# bb-psu-mk-1_2.net
KiCad netlist of a schematic drawn in EAGLE
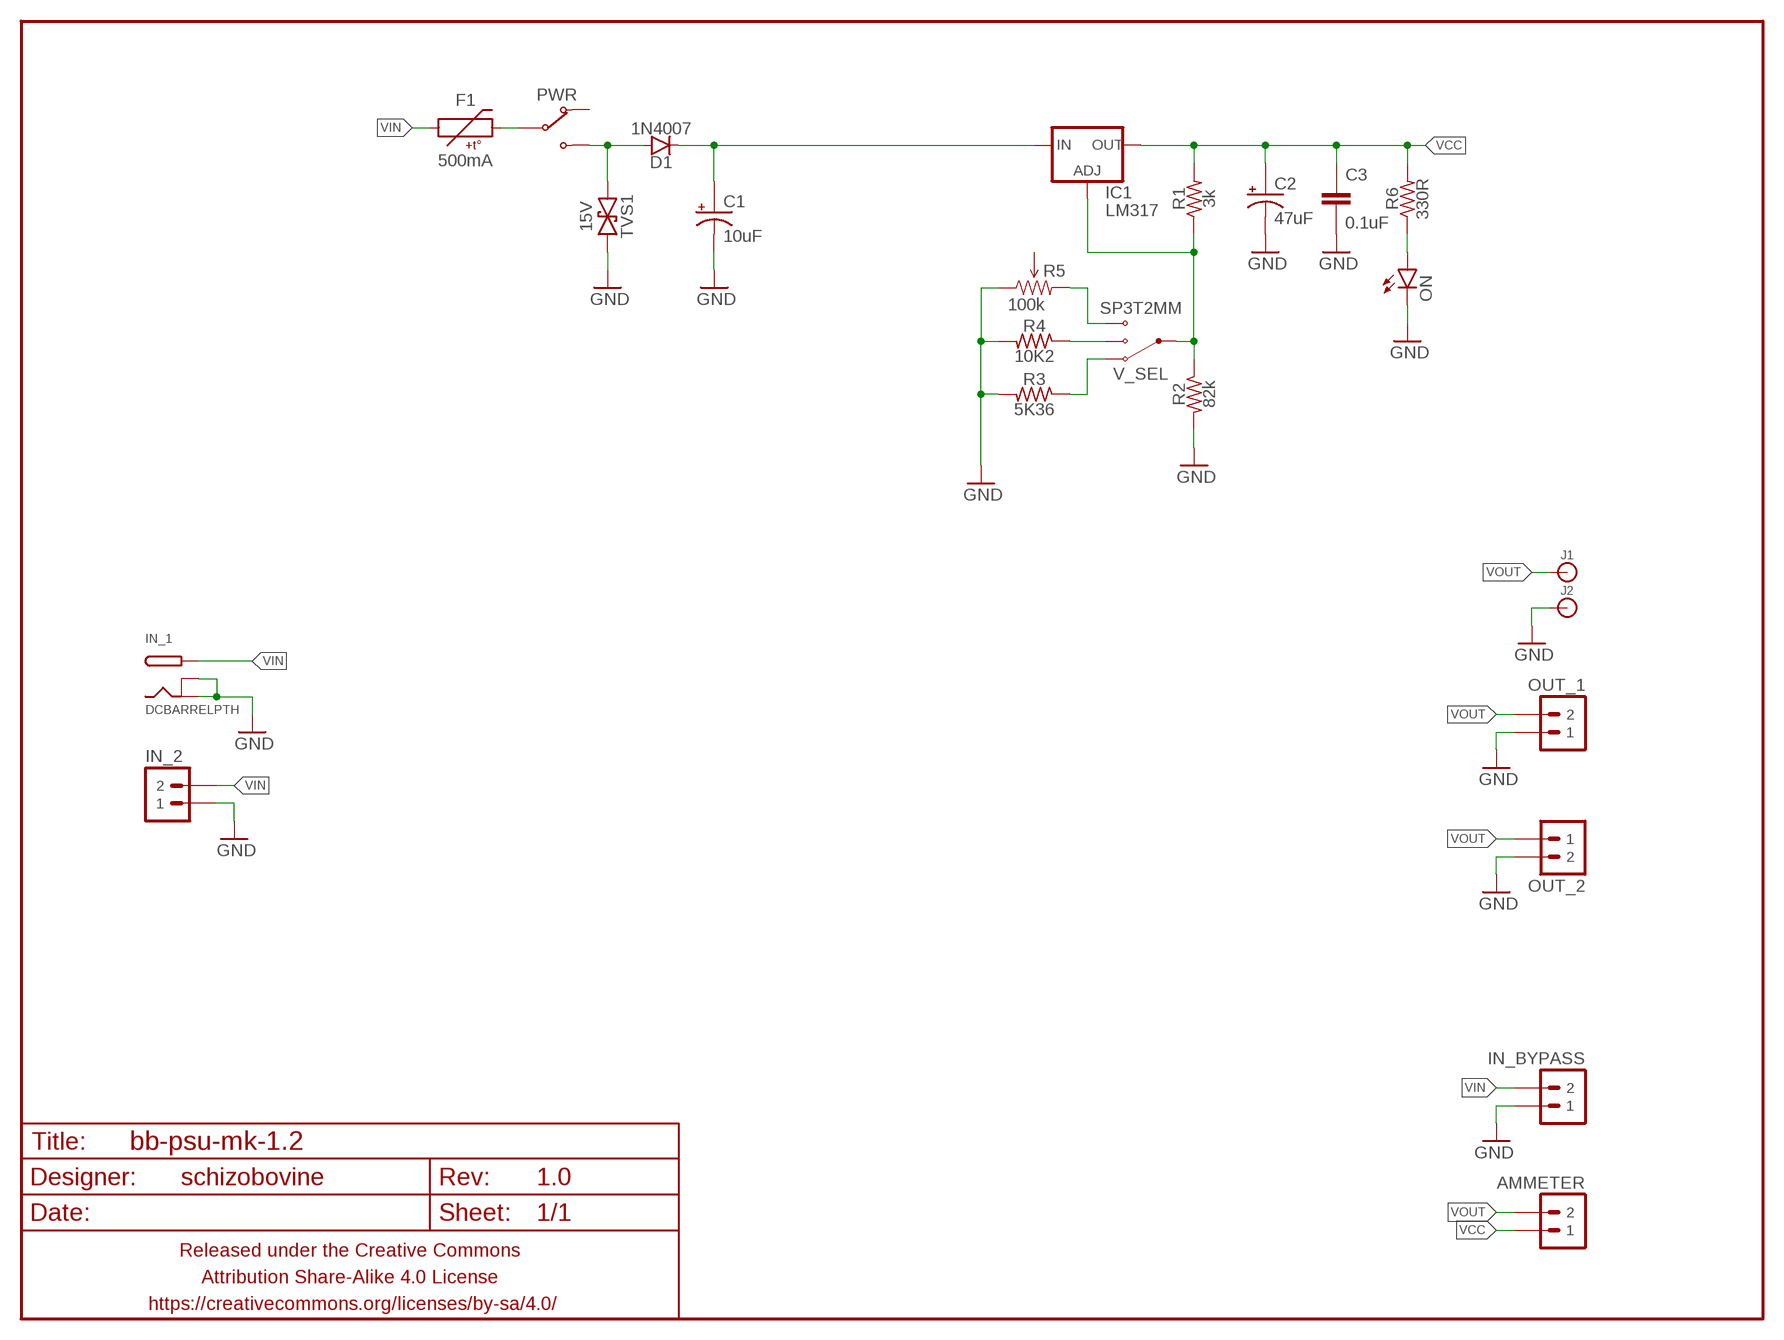
[diagram p0: schematic, sheet 1]

(export (version "E")
  (design (tool "Eeschema 10.0.6"))
  (components
    (comp (ref "AMMETER")
      (value "M02PTH-CENTERED")
      (footprint "eagle-import:1X02-CENTER")
      (libsource (lib "eagle-import") (part "M02PTH-CENTERED"))
    )
    (comp (ref "C1")
      (value "10uF")
      (footprint "eagle-import:E2,5-6")
      (libsource (lib "eagle-import") (part "CAPACITOR-POLARIZEDE2.5-6"))
    )
    (comp (ref "C2")
      (value "47uF")
      (footprint "eagle-import:E2,5-6")
      (libsource (lib "eagle-import") (part "CAPACITOR-POLARIZEDE2.5-6"))
    )
    (comp (ref "C3")
      (value "0.1uF")
      (footprint "eagle-import:C025-024X044")
      (libsource (lib "eagle-import") (part "CAPACITOR-CERAMIC025-024X044"))
    )
    (comp (ref "D1")
      (value "1N4007")
      (footprint "eagle-import:DIODE-10.16MM")
      (libsource (lib "eagle-import") (part "DIODEPTH-10.68MM"))
    )
    (comp (ref "F1")
      (value "500mA")
      (footprint "eagle-import:PTC-PTH-5.08MM")
      (libsource (lib "eagle-import") (part "PTCPTH-5.08MM"))
    )
    (comp (ref "FRAME1")
      (value "FRAME-LETTERNO_PACKAGE")
      (footprint "eagle-import:DUMMY")
      (fields (field (name "DESIGNER") "schizobovine") (field (name "VERSION") "1.0"))
      (libsource (lib "eagle-import") (part "FRAME-LETTERNO_PACKAGE"))
    )
    (comp (ref "IC1")
      (value "LM317")
      (footprint "eagle-import:TO220-THERMPAD")
      (libsource (lib "eagle-import") (part "V_REG_317THERMPAD"))
    )
    (comp (ref "IN_1")
      (value "DCBARRELPTH")
      (footprint "eagle-import:DCJACK_2MM_PTH")
      (libsource (lib "eagle-import") (part "DCBARRELPTH"))
    )
    (comp (ref "IN_2")
      (value "M02PTH-CENTERED-R+")
      (footprint "eagle-import:1X02-CENTER-R+")
      (libsource (lib "eagle-import") (part "M02PTH-CENTERED-R+"))
    )
    (comp (ref "IN_BYPASS")
      (value "M02PTH-CENTERED-R+")
      (footprint "eagle-import:1X02-CENTER-R+")
      (libsource (lib "eagle-import") (part "M02PTH-CENTERED-R+"))
    )
    (comp (ref "J1")
      (value "BANANA_CONNPOAST")
      (footprint "eagle-import:BINDING_POST")
      (libsource (lib "eagle-import") (part "BANANA_CONNPOAST"))
    )
    (comp (ref "J2")
      (value "BANANA_CONNPOAST")
      (footprint "eagle-import:BINDING_POST")
      (libsource (lib "eagle-import") (part "BANANA_CONNPOAST"))
    )
    (comp (ref "ON")
      (value "LED3MM-LESS")
      (footprint "eagle-import:LED3MM-LESSSILK")
      (libsource (lib "eagle-import") (part "LED3MM-LESS"))
    )
    (comp (ref "OUT_1")
      (value "M02PTH-CENTERED-R+")
      (footprint "eagle-import:1X02-CENTER-R+")
      (libsource (lib "eagle-import") (part "M02PTH-CENTERED-R+"))
    )
    (comp (ref "OUT_2")
      (value "M023.5MM")
      (footprint "eagle-import:SCREWTERMINAL-3.5MM-2")
      (libsource (lib "eagle-import") (part "M023.5MM"))
    )
    (comp (ref "PWR")
      (value "SWITCH-SPDTPTH-VERT-2.54MM")
      (footprint "eagle-import:SWITCH-SPDT")
      (libsource (lib "eagle-import") (part "SWITCH-SPDTPTH-VERT-2.54MM"))
    )
    (comp (ref "R1")
      (value "3k")
      (footprint "eagle-import:RESISTOR-AXIAL-PTH-7.62MM")
      (libsource (lib "eagle-import") (part "RESISTORPTH-AXIAL-7.62MM"))
    )
    (comp (ref "R2")
      (value "82k")
      (footprint "eagle-import:RESISTOR-AXIAL-PTH-7.62MM")
      (libsource (lib "eagle-import") (part "RESISTORPTH-AXIAL-7.62MM"))
    )
    (comp (ref "R3")
      (value "5K36")
      (footprint "eagle-import:RESISTOR-AXIAL-PTH-7.62MM")
      (libsource (lib "eagle-import") (part "RESISTORPTH-AXIAL-7.62MM"))
    )
    (comp (ref "R4")
      (value "10K2")
      (footprint "eagle-import:RESISTOR-AXIAL-PTH-7.62MM")
      (libsource (lib "eagle-import") (part "RESISTORPTH-AXIAL-7.62MM"))
    )
    (comp (ref "R5")
      (value "100k")
      (footprint "eagle-import:3386U")
      (libsource (lib "eagle-import") (part "TRIMPOT-PTH-KNOB"))
    )
    (comp (ref "R6")
      (value "330R")
      (footprint "eagle-import:RESISTOR-AXIAL-PTH-6.35MM")
      (libsource (lib "eagle-import") (part "RESISTORPTH-AXIAL-6.35MM"))
    )
    (comp (ref "TVS1")
      (value "15V")
      (footprint "eagle-import:DO-41-TVS-BI-10.16MM")
      (libsource (lib "eagle-import") (part "TVSDO-41-10.16MM"))
    )
    (comp (ref "V_SEL")
      (value "SP3T2MM")
      (footprint "eagle-import:SP3T-2MM")
      (libsource (lib "eagle-import") (part "SP3T2MM"))
    )
  )
  (nets
    (net (code "1") (name "GND") (class "Default")
      (node (ref "C1") (pin "-") (pinfunction "-_-") (pintype "passive"))
      (node (ref "C2") (pin "-") (pinfunction "-_-") (pintype "passive"))
      (node (ref "C3") (pin "2") (pinfunction "2_2") (pintype "passive"))
      (node (ref "IN_1") (pin "BRK") (pinfunction "BRK_BRK") (pintype "bidirectional"))
      (node (ref "IN_1") (pin "GND") (pinfunction "GND_GND") (pintype "bidirectional"))
      (node (ref "IN_2") (pin "1") (pinfunction "1_1") (pintype "passive"))
      (node (ref "IN_BYPASS") (pin "1") (pinfunction "1_1") (pintype "passive"))
      (node (ref "J2") (pin "P$1") (pinfunction "1_P$1") (pintype "passive"))
      (node (ref "ON") (pin "K") (pinfunction "C_K") (pintype "passive"))
      (node (ref "OUT_1") (pin "1") (pinfunction "1_1") (pintype "passive"))
      (node (ref "OUT_2") (pin "2") (pinfunction "2_2") (pintype "passive"))
      (node (ref "R2") (pin "P$2") (pinfunction "2_P$2") (pintype "passive"))
      (node (ref "R3") (pin "P$2") (pinfunction "2_P$2") (pintype "passive"))
      (node (ref "R4") (pin "P$2") (pinfunction "2_P$2") (pintype "passive"))
      (node (ref "R5") (pin "1") (pinfunction "CCW_1") (pintype "passive"))
      (node (ref "TVS1") (pin "P$2") (pinfunction "2_P$2") (pintype "passive"))
    )
    (net (code "2") (name "Net-(F1-2)") (class "Default")
      (node (ref "F1") (pin "P$2") (pinfunction "2_P$2") (pintype "passive"))
      (node (ref "PWR") (pin "2") (pinfunction "COM_2") (pintype "passive"))
    )
    (net (code "3") (name "Net-(IC1-ADJ)") (class "Default")
      (node (ref "IC1") (pin "1") (pinfunction "ADJ_1") (pintype "input"))
      (node (ref "R1") (pin "P$1") (pinfunction "1_P$1") (pintype "passive"))
      (node (ref "R2") (pin "P$1") (pinfunction "1_P$1") (pintype "passive"))
      (node (ref "V_SEL") (pin "P$1") (pinfunction "COM_P$1") (pintype "bidirectional"))
    )
    (net (code "4") (name "Net-(IC1-IN)") (class "Default")
      (node (ref "C1") (pin "+") (pinfunction "+_+") (pintype "passive"))
      (node (ref "D1") (pin "C") (pinfunction "C_C") (pintype "passive"))
      (node (ref "IC1") (pin "3") (pinfunction "IN_3") (pintype "input"))
    )
    (net (code "5") (name "Net-(PWR-NO)") (class "Default")
      (node (ref "D1") (pin "A") (pinfunction "A_A") (pintype "passive"))
      (node (ref "PWR") (pin "3") (pinfunction "NO_3") (pintype "passive"))
      (node (ref "TVS1") (pin "P$1") (pinfunction "1_P$1") (pintype "passive"))
    )
    (net (code "6") (name "Net-(R3-1)") (class "Default")
      (node (ref "R3") (pin "P$1") (pinfunction "1_P$1") (pintype "passive"))
      (node (ref "V_SEL") (pin "P$2") (pinfunction "A_P$2") (pintype "bidirectional"))
    )
    (net (code "7") (name "Net-(R4-1)") (class "Default")
      (node (ref "R4") (pin "P$1") (pinfunction "1_P$1") (pintype "passive"))
      (node (ref "V_SEL") (pin "P$3") (pinfunction "B_P$3") (pintype "bidirectional"))
    )
    (net (code "8") (name "Net-(R5-CW)") (class "Default")
      (node (ref "R5") (pin "3") (pinfunction "CW_3") (pintype "passive"))
      (node (ref "V_SEL") (pin "P$4") (pinfunction "C_P$4") (pintype "bidirectional"))
    )
    (net (code "9") (name "Net-(R6-1)") (class "Default")
      (node (ref "ON") (pin "A") (pinfunction "A_A") (pintype "passive"))
      (node (ref "R6") (pin "P$1") (pinfunction "1_P$1") (pintype "passive"))
    )
    (net (code "10") (name "VCC") (class "Default")
      (node (ref "AMMETER") (pin "1") (pinfunction "1_1") (pintype "passive"))
      (node (ref "C2") (pin "+") (pinfunction "+_+") (pintype "passive"))
      (node (ref "C3") (pin "1") (pinfunction "1_1") (pintype "passive"))
      (node (ref "IC1") (pin "2@1") (pinfunction "OUT_2@1") (pintype "output"))
      (node (ref "IC1") (pin "2@2") (pinfunction "OUT_2@2") (pintype "output"))
      (node (ref "R1") (pin "P$2") (pinfunction "2_P$2") (pintype "passive"))
      (node (ref "R6") (pin "P$2") (pinfunction "2_P$2") (pintype "passive"))
    )
    (net (code "11") (name "VIN") (class "Default")
      (node (ref "F1") (pin "P$1") (pinfunction "1_P$1") (pintype "passive"))
      (node (ref "IN_1") (pin "PWR") (pinfunction "PWR_PWR") (pintype "bidirectional"))
      (node (ref "IN_2") (pin "2") (pinfunction "2_2") (pintype "passive"))
      (node (ref "IN_BYPASS") (pin "2") (pinfunction "2_2") (pintype "passive"))
    )
    (net (code "12") (name "VOUT") (class "Default")
      (node (ref "AMMETER") (pin "2") (pinfunction "2_2") (pintype "passive"))
      (node (ref "J1") (pin "P$1") (pinfunction "1_P$1") (pintype "passive"))
      (node (ref "OUT_1") (pin "2") (pinfunction "2_2") (pintype "passive"))
      (node (ref "OUT_2") (pin "1") (pinfunction "1_1") (pintype "passive"))
    )
    (net (code "13") (name "unconnected-(PWR-NC-Pad1)") (class "Default")
      (node (ref "PWR") (pin "1") (pinfunction "NC_1") (pintype "passive"))
    )
    (net (code "14") (name "unconnected-(R5-WIPER-Pad2)") (class "Default")
      (node (ref "R5") (pin "2") (pinfunction "WIPER_2") (pintype "passive"))
    )
  )
)
